# analog_tlv379_buffer.net
KiCad netlist of a schematic drawn in Altium Designer
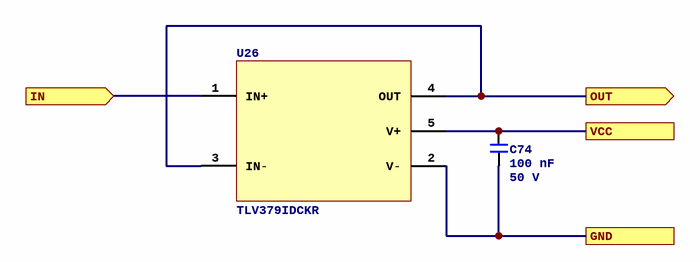
[diagram p0: analog_tlv379_buffer.SchDoc]

(export (version "E")
  (design (tool "Eeschema 10.0.6"))
  (components
    (comp (ref "C74")
      (value "CL05B104KB54PNC")
      (footprint "C0402")
      (fields
        (field (name "CAPACITANCE") "100 nF")
        (field (name "MANUFACTURER") "Samsung Electro-Mechanics")
        (field (name "VOLTAGE RATING") "50 V")
      )
      (libsource (lib "database") (part "__template_cap"))
    )
    (comp (ref "U26")
      (value "TLV379IDCKR")
      (footprint "5SC70")
      (fields (field (name "MANUFACTURER") "Texas Instruments"))
      (libsource (lib "database") (part "TLV379IDCKR"))
    )
  )
  (nets
    (net (code "1") (name "/GND") (class "Default")
      (node (ref "C74") (pin "2") (pintype "passive"))
      (node (ref "U26") (pin "2") (pinfunction "V-_2") (pintype "passive"))
    )
    (net (code "2") (name "/IN") (class "Default")
      (node (ref "U26") (pin "1") (pinfunction "IN+_1") (pintype "passive"))
    )
    (net (code "3") (name "/OUT") (class "Default")
      (node (ref "U26") (pin "3") (pinfunction "IN-_3") (pintype "passive"))
      (node (ref "U26") (pin "4") (pinfunction "OUT_4") (pintype "passive"))
    )
    (net (code "4") (name "/VCC") (class "Default")
      (node (ref "C74") (pin "1") (pintype "passive"))
      (node (ref "U26") (pin "5") (pinfunction "V+_5") (pintype "passive"))
    )
  )
)
